# JOYSTICK.net
KiCad netlist of a schematic drawn in EAGLE
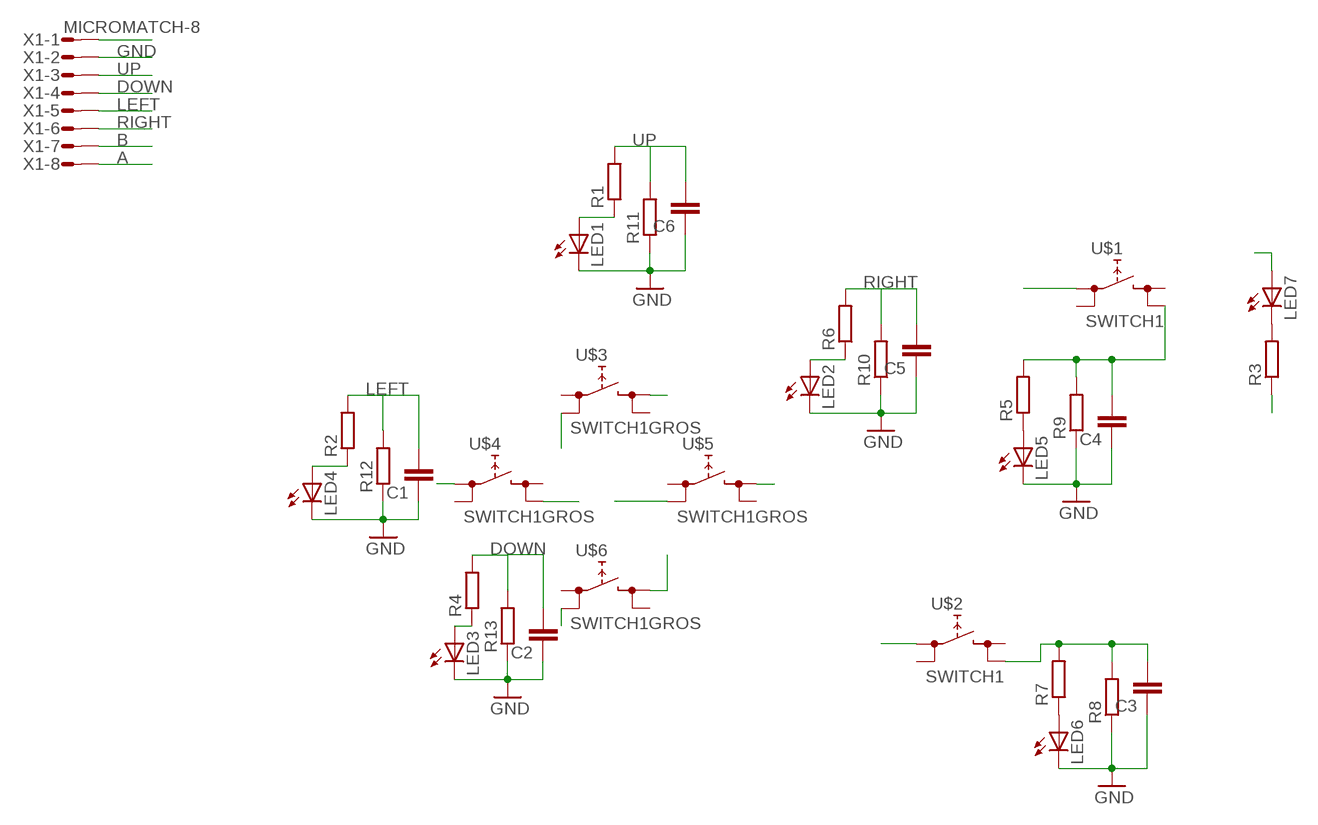
[diagram p0: schematic, sheet 1]

(export (version "E")
  (design (tool "Eeschema 10.0.6"))
  (components
    (comp (ref "C1")
      (value "C-EUC0805")
      (footprint "eagle-import:C0805")
      (libsource (lib "eagle-import") (part "C-EUC0805"))
    )
    (comp (ref "C2")
      (value "C-EUC0805")
      (footprint "eagle-import:C0805")
      (libsource (lib "eagle-import") (part "C-EUC0805"))
    )
    (comp (ref "C3")
      (value "C-EUC0805")
      (footprint "eagle-import:C0805")
      (libsource (lib "eagle-import") (part "C-EUC0805"))
    )
    (comp (ref "C4")
      (value "C-EUC0805")
      (footprint "eagle-import:C0805")
      (libsource (lib "eagle-import") (part "C-EUC0805"))
    )
    (comp (ref "C5")
      (value "C-EUC0805")
      (footprint "eagle-import:C0805")
      (libsource (lib "eagle-import") (part "C-EUC0805"))
    )
    (comp (ref "C6")
      (value "C-EUC0805")
      (footprint "eagle-import:C0805")
      (libsource (lib "eagle-import") (part "C-EUC0805"))
    )
    (comp (ref "LED1")
      (value "LED3MM")
      (footprint "eagle-import:LED3MM")
      (libsource (lib "eagle-import") (part "LED3MM"))
    )
    (comp (ref "LED2")
      (value "LED3MM")
      (footprint "eagle-import:LED3MM")
      (libsource (lib "eagle-import") (part "LED3MM"))
    )
    (comp (ref "LED3")
      (value "LED3MM")
      (footprint "eagle-import:LED3MM")
      (libsource (lib "eagle-import") (part "LED3MM"))
    )
    (comp (ref "LED4")
      (value "LED3MM")
      (footprint "eagle-import:LED3MM")
      (libsource (lib "eagle-import") (part "LED3MM"))
    )
    (comp (ref "LED5")
      (value "LED3MM")
      (footprint "eagle-import:LED3MM")
      (libsource (lib "eagle-import") (part "LED3MM"))
    )
    (comp (ref "LED6")
      (value "LED3MM")
      (footprint "eagle-import:LED3MM")
      (libsource (lib "eagle-import") (part "LED3MM"))
    )
    (comp (ref "LED7")
      (value "LED3MM")
      (footprint "eagle-import:LED3MM")
      (libsource (lib "eagle-import") (part "LED3MM"))
    )
    (comp (ref "R1")
      (value "R-EU_R0805")
      (footprint "eagle-import:R0805")
      (libsource (lib "eagle-import") (part "R-EU_R0805"))
    )
    (comp (ref "R2")
      (value "R-EU_R0805")
      (footprint "eagle-import:R0805")
      (libsource (lib "eagle-import") (part "R-EU_R0805"))
    )
    (comp (ref "R3")
      (value "R-EU_R0805")
      (footprint "eagle-import:R0805")
      (libsource (lib "eagle-import") (part "R-EU_R0805"))
    )
    (comp (ref "R4")
      (value "R-EU_R0805")
      (footprint "eagle-import:R0805")
      (libsource (lib "eagle-import") (part "R-EU_R0805"))
    )
    (comp (ref "R5")
      (value "R-EU_R0805")
      (footprint "eagle-import:R0805")
      (libsource (lib "eagle-import") (part "R-EU_R0805"))
    )
    (comp (ref "R6")
      (value "R-EU_R0805")
      (footprint "eagle-import:R0805")
      (libsource (lib "eagle-import") (part "R-EU_R0805"))
    )
    (comp (ref "R7")
      (value "R-EU_R0805")
      (footprint "eagle-import:R0805")
      (libsource (lib "eagle-import") (part "R-EU_R0805"))
    )
    (comp (ref "R8")
      (value "R-EU_R0805")
      (footprint "eagle-import:R0805")
      (libsource (lib "eagle-import") (part "R-EU_R0805"))
    )
    (comp (ref "R9")
      (value "R-EU_R0805")
      (footprint "eagle-import:R0805")
      (libsource (lib "eagle-import") (part "R-EU_R0805"))
    )
    (comp (ref "R10")
      (value "R-EU_R0805")
      (footprint "eagle-import:R0805")
      (libsource (lib "eagle-import") (part "R-EU_R0805"))
    )
    (comp (ref "R11")
      (value "R-EU_R0805")
      (footprint "eagle-import:R0805")
      (libsource (lib "eagle-import") (part "R-EU_R0805"))
    )
    (comp (ref "R12")
      (value "R-EU_R0805")
      (footprint "eagle-import:R0805")
      (libsource (lib "eagle-import") (part "R-EU_R0805"))
    )
    (comp (ref "R13")
      (value "R-EU_R0805")
      (footprint "eagle-import:R0805")
      (libsource (lib "eagle-import") (part "R-EU_R0805"))
    )
    (comp (ref "U$1")
      (value "SWITCH1")
      (footprint "eagle-import:TL1105")
      (libsource (lib "eagle-import") (part "SWITCH1"))
    )
    (comp (ref "U$2")
      (value "SWITCH1")
      (footprint "eagle-import:TL1105")
      (libsource (lib "eagle-import") (part "SWITCH1"))
    )
    (comp (ref "U$3")
      (value "SWITCH1GROS")
      (footprint "eagle-import:REKN")
      (libsource (lib "eagle-import") (part "SWITCH1GROS"))
    )
    (comp (ref "U$4")
      (value "SWITCH1GROS")
      (footprint "eagle-import:REKN")
      (libsource (lib "eagle-import") (part "SWITCH1GROS"))
    )
    (comp (ref "U$5")
      (value "SWITCH1GROS")
      (footprint "eagle-import:REKN")
      (libsource (lib "eagle-import") (part "SWITCH1GROS"))
    )
    (comp (ref "U$6")
      (value "SWITCH1GROS")
      (footprint "eagle-import:REKN")
      (libsource (lib "eagle-import") (part "SWITCH1GROS"))
    )
    (comp (ref "X1")
      (value "MICROMATCH-8")
      (footprint "eagle-import:MICROMATCH-8")
      (fields (field (name "MF") "FARNELL") (field (name "MPN") "7-215464-8"))
      (libsource (lib "eagle-import") (part "MICROMATCH-8"))
    )
  )
  (nets
    (net (code "1") (name "/+5V") (class "Default")
      (node (ref "LED7") (pin "A") (pinfunction "A_A") (pintype "passive"))
      (node (ref "U$1") (pin "1") (pinfunction "0_1") (pintype "passive"))
      (node (ref "U$2") (pin "1") (pinfunction "0_1") (pintype "passive"))
      (node (ref "U$3") (pin "1B") (pinfunction "0_1B") (pintype "passive"))
      (node (ref "U$4") (pin "2B") (pinfunction "1_2B") (pintype "passive"))
      (node (ref "U$5") (pin "1B") (pinfunction "0_1B") (pintype "passive"))
      (node (ref "U$6") (pin "2A") (pinfunction "1_2A") (pintype "passive"))
      (node (ref "X1") (pin "1") (pinfunction "S_1") (pintype "passive"))
    )
    (net (code "2") (name "/A") (class "Default")
      (node (ref "C4") (pin "2") (pinfunction "2_2") (pintype "passive"))
      (node (ref "R5") (pin "2") (pinfunction "2_2") (pintype "passive"))
      (node (ref "R9") (pin "2") (pinfunction "2_2") (pintype "passive"))
      (node (ref "U$1") (pin "4") (pinfunction "1_4") (pintype "passive"))
      (node (ref "X1") (pin "8") (pinfunction "S_8") (pintype "passive"))
    )
    (net (code "3") (name "/B") (class "Default")
      (node (ref "C3") (pin "2") (pinfunction "2_2") (pintype "passive"))
      (node (ref "R7") (pin "2") (pinfunction "2_2") (pintype "passive"))
      (node (ref "R8") (pin "2") (pinfunction "2_2") (pintype "passive"))
      (node (ref "U$2") (pin "4") (pinfunction "1_4") (pintype "passive"))
      (node (ref "X1") (pin "7") (pinfunction "S_7") (pintype "passive"))
    )
    (net (code "4") (name "/DOWN") (class "Default")
      (node (ref "C2") (pin "2") (pinfunction "2_2") (pintype "passive"))
      (node (ref "R13") (pin "2") (pinfunction "2_2") (pintype "passive"))
      (node (ref "R4") (pin "2") (pinfunction "2_2") (pintype "passive"))
      (node (ref "U$6") (pin "1B") (pinfunction "0_1B") (pintype "passive"))
      (node (ref "X1") (pin "4") (pinfunction "S_4") (pintype "passive"))
    )
    (net (code "5") (name "/LEFT") (class "Default")
      (node (ref "C1") (pin "2") (pinfunction "2_2") (pintype "passive"))
      (node (ref "R12") (pin "2") (pinfunction "2_2") (pintype "passive"))
      (node (ref "R2") (pin "2") (pinfunction "2_2") (pintype "passive"))
      (node (ref "U$4") (pin "1A") (pinfunction "0_1A") (pintype "passive"))
      (node (ref "X1") (pin "5") (pinfunction "S_5") (pintype "passive"))
    )
    (net (code "6") (name "/RIGHT") (class "Default")
      (node (ref "C5") (pin "2") (pinfunction "2_2") (pintype "passive"))
      (node (ref "R10") (pin "2") (pinfunction "2_2") (pintype "passive"))
      (node (ref "R6") (pin "2") (pinfunction "2_2") (pintype "passive"))
      (node (ref "U$5") (pin "2A") (pinfunction "1_2A") (pintype "passive"))
      (node (ref "X1") (pin "6") (pinfunction "S_6") (pintype "passive"))
    )
    (net (code "7") (name "/UP") (class "Default")
      (node (ref "C6") (pin "2") (pinfunction "2_2") (pintype "passive"))
      (node (ref "R1") (pin "2") (pinfunction "2_2") (pintype "passive"))
      (node (ref "R11") (pin "2") (pinfunction "2_2") (pintype "passive"))
      (node (ref "U$3") (pin "2A") (pinfunction "1_2A") (pintype "passive"))
      (node (ref "X1") (pin "3") (pinfunction "S_3") (pintype "passive"))
    )
    (net (code "8") (name "GND") (class "Default")
      (node (ref "C1") (pin "1") (pinfunction "1_1") (pintype "passive"))
      (node (ref "C2") (pin "1") (pinfunction "1_1") (pintype "passive"))
      (node (ref "C3") (pin "1") (pinfunction "1_1") (pintype "passive"))
      (node (ref "C4") (pin "1") (pinfunction "1_1") (pintype "passive"))
      (node (ref "C5") (pin "1") (pinfunction "1_1") (pintype "passive"))
      (node (ref "C6") (pin "1") (pinfunction "1_1") (pintype "passive"))
      (node (ref "LED1") (pin "K") (pinfunction "C_K") (pintype "passive"))
      (node (ref "LED2") (pin "K") (pinfunction "C_K") (pintype "passive"))
      (node (ref "LED3") (pin "K") (pinfunction "C_K") (pintype "passive"))
      (node (ref "LED4") (pin "K") (pinfunction "C_K") (pintype "passive"))
      (node (ref "LED5") (pin "K") (pinfunction "C_K") (pintype "passive"))
      (node (ref "LED6") (pin "K") (pinfunction "C_K") (pintype "passive"))
      (node (ref "R10") (pin "1") (pinfunction "1_1") (pintype "passive"))
      (node (ref "R11") (pin "1") (pinfunction "1_1") (pintype "passive"))
      (node (ref "R12") (pin "1") (pinfunction "1_1") (pintype "passive"))
      (node (ref "R13") (pin "1") (pinfunction "1_1") (pintype "passive"))
      (node (ref "R3") (pin "1") (pinfunction "1_1") (pintype "passive"))
      (node (ref "R8") (pin "1") (pinfunction "1_1") (pintype "passive"))
      (node (ref "R9") (pin "1") (pinfunction "1_1") (pintype "passive"))
      (node (ref "X1") (pin "2") (pinfunction "S_2") (pintype "passive"))
    )
    (net (code "9") (name "Net-(LED1-PadA)") (class "Default")
      (node (ref "LED1") (pin "A") (pinfunction "A_A") (pintype "passive"))
      (node (ref "R1") (pin "1") (pinfunction "1_1") (pintype "passive"))
    )
    (net (code "10") (name "Net-(LED2-PadA)") (class "Default")
      (node (ref "LED2") (pin "A") (pinfunction "A_A") (pintype "passive"))
      (node (ref "R6") (pin "1") (pinfunction "1_1") (pintype "passive"))
    )
    (net (code "11") (name "Net-(LED3-PadA)") (class "Default")
      (node (ref "LED3") (pin "A") (pinfunction "A_A") (pintype "passive"))
      (node (ref "R4") (pin "1") (pinfunction "1_1") (pintype "passive"))
    )
    (net (code "12") (name "Net-(LED4-PadA)") (class "Default")
      (node (ref "LED4") (pin "A") (pinfunction "A_A") (pintype "passive"))
      (node (ref "R2") (pin "1") (pinfunction "1_1") (pintype "passive"))
    )
    (net (code "13") (name "Net-(LED5-PadA)") (class "Default")
      (node (ref "LED5") (pin "A") (pinfunction "A_A") (pintype "passive"))
      (node (ref "R5") (pin "1") (pinfunction "1_1") (pintype "passive"))
    )
    (net (code "14") (name "Net-(LED6-PadA)") (class "Default")
      (node (ref "LED6") (pin "A") (pinfunction "A_A") (pintype "passive"))
      (node (ref "R7") (pin "1") (pinfunction "1_1") (pintype "passive"))
    )
    (net (code "15") (name "Net-(LED7-C)") (class "Default")
      (node (ref "LED7") (pin "K") (pinfunction "C_K") (pintype "passive"))
      (node (ref "R3") (pin "2") (pinfunction "2_2") (pintype "passive"))
    )
    (net (code "16") (name "unconnected-(U$1-0-Pad2)") (class "Default")
      (node (ref "U$1") (pin "2") (pinfunction "0_2") (pintype "passive"))
    )
    (net (code "17") (name "unconnected-(U$1-1-Pad3)") (class "Default")
      (node (ref "U$1") (pin "3") (pinfunction "1_3") (pintype "passive"))
    )
    (net (code "18") (name "unconnected-(U$2-0-Pad2)") (class "Default")
      (node (ref "U$2") (pin "2") (pinfunction "0_2") (pintype "passive"))
    )
    (net (code "19") (name "unconnected-(U$2-1-Pad3)") (class "Default")
      (node (ref "U$2") (pin "3") (pinfunction "1_3") (pintype "passive"))
    )
    (net (code "20") (name "unconnected-(U$3-0-Pad1A)") (class "Default")
      (node (ref "U$3") (pin "1A") (pinfunction "0_1A") (pintype "passive"))
    )
    (net (code "21") (name "unconnected-(U$3-1-Pad2B)") (class "Default")
      (node (ref "U$3") (pin "2B") (pinfunction "1_2B") (pintype "passive"))
    )
    (net (code "22") (name "unconnected-(U$4-0-Pad1B)") (class "Default")
      (node (ref "U$4") (pin "1B") (pinfunction "0_1B") (pintype "passive"))
    )
    (net (code "23") (name "unconnected-(U$4-1-Pad2A)") (class "Default")
      (node (ref "U$4") (pin "2A") (pinfunction "1_2A") (pintype "passive"))
    )
    (net (code "24") (name "unconnected-(U$5-0-Pad1A)") (class "Default")
      (node (ref "U$5") (pin "1A") (pinfunction "0_1A") (pintype "passive"))
    )
    (net (code "25") (name "unconnected-(U$5-1-Pad2B)") (class "Default")
      (node (ref "U$5") (pin "2B") (pinfunction "1_2B") (pintype "passive"))
    )
    (net (code "26") (name "unconnected-(U$6-0-Pad1A)") (class "Default")
      (node (ref "U$6") (pin "1A") (pinfunction "0_1A") (pintype "passive"))
    )
    (net (code "27") (name "unconnected-(U$6-1-Pad2B)") (class "Default")
      (node (ref "U$6") (pin "2B") (pinfunction "1_2B") (pintype "passive"))
    )
  )
)
